# uSDcard.net
KiCad netlist of a schematic drawn in Altium Designer
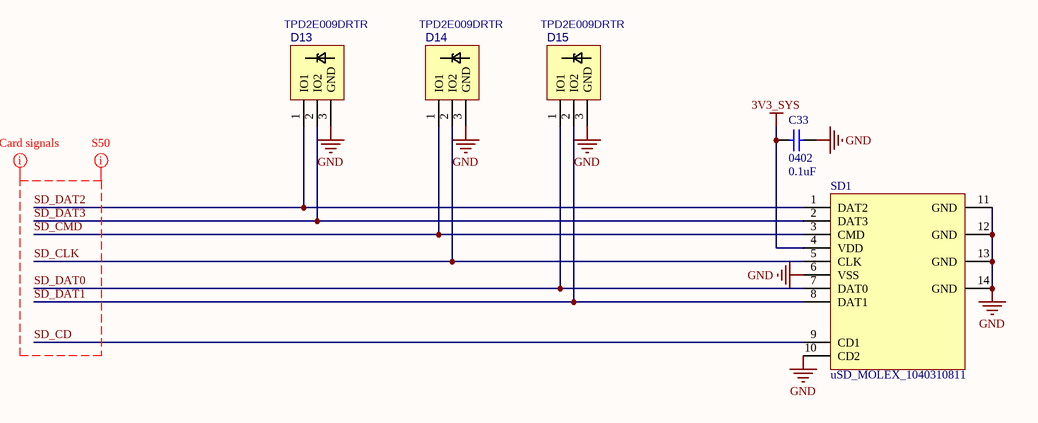
[diagram p0: uSDcard.SchDoc]

(export (version "E")
  (design (tool "Eeschema 10.0.6"))
  (components
    (comp (ref "C33")
      (value "0402")
      (footprint "cap0402")
      (description "standard, non-polarized capacitor")
      (fields (field (name "ALTIUM_VALUE") "0.1uF"))
      (libsource (lib "capacitor") (part "cap"))
    )
    (comp (ref "D13")
      (value "TPD2E009DRTR")
      (footprint "SOT-3")
      (description "ESD Suppressors 2-CH")
      (fields (field (name "MANUFACTURER") "Texas Instruments"))
      (libsource (lib "jetson-nano-baseboard-rev.1.0") (part "TPD2E009"))
    )
    (comp (ref "D14")
      (value "TPD2E009DRTR")
      (footprint "SOT-3")
      (description "ESD Suppressors 2-CH")
      (fields (field (name "MANUFACTURER") "Texas Instruments"))
      (libsource (lib "jetson-nano-baseboard-rev.1.0") (part "TPD2E009"))
    )
    (comp (ref "D15")
      (value "TPD2E009DRTR")
      (footprint "SOT-3")
      (description "ESD Suppressors 2-CH")
      (fields (field (name "MANUFACTURER") "Texas Instruments"))
      (libsource (lib "jetson-nano-baseboard-rev.1.0") (part "TPD2E009"))
    )
    (comp (ref "SD1")
      (value "uSD_MOLEX_1040310811")
      (footprint "uSD_MOLEX_1040310811")
      (libsource (lib "card_holder") (part "uSD_MOLEX_1040310811"))
    )
  )
  (nets
    (net (code "1") (name "/SD_CD") (class "Default")
      (node (ref "SD1") (pin "9") (pinfunction "CD1_9") (pintype "passive"))
    )
    (net (code "2") (name "/SD_CLK") (class "Default")
      (node (ref "D14") (pin "2") (pinfunction "IO2_2") (pintype "passive"))
      (node (ref "SD1") (pin "5") (pinfunction "CLK_5") (pintype "passive"))
    )
    (net (code "3") (name "/SD_CMD") (class "Default")
      (node (ref "D14") (pin "1") (pinfunction "IO1_1") (pintype "passive"))
      (node (ref "SD1") (pin "3") (pinfunction "CMD_3") (pintype "passive"))
    )
    (net (code "4") (name "/SD_DAT0") (class "Default")
      (node (ref "D15") (pin "1") (pinfunction "IO1_1") (pintype "passive"))
      (node (ref "SD1") (pin "7") (pinfunction "DAT0_7") (pintype "passive"))
    )
    (net (code "5") (name "/SD_DAT1") (class "Default")
      (node (ref "D15") (pin "2") (pinfunction "IO2_2") (pintype "passive"))
      (node (ref "SD1") (pin "8") (pinfunction "DAT1_8") (pintype "passive"))
    )
    (net (code "6") (name "/SD_DAT2") (class "Default")
      (node (ref "D13") (pin "1") (pinfunction "IO1_1") (pintype "passive"))
      (node (ref "SD1") (pin "1") (pinfunction "DAT2_1") (pintype "passive"))
    )
    (net (code "7") (name "/SD_DAT3") (class "Default")
      (node (ref "D13") (pin "2") (pinfunction "IO2_2") (pintype "passive"))
      (node (ref "SD1") (pin "2") (pinfunction "DAT3_2") (pintype "passive"))
    )
    (net (code "8") (name "3V3_SYS") (class "Default")
      (node (ref "C33") (pin "1") (pinfunction "1_1") (pintype "passive"))
      (node (ref "SD1") (pin "4") (pinfunction "VDD_4") (pintype "passive"))
    )
    (net (code "9") (name "GND") (class "Default")
      (node (ref "C33") (pin "2") (pinfunction "2_2") (pintype "passive"))
      (node (ref "D13") (pin "3") (pinfunction "GND_3") (pintype "passive"))
      (node (ref "D14") (pin "3") (pinfunction "GND_3") (pintype "passive"))
      (node (ref "D15") (pin "3") (pinfunction "GND_3") (pintype "passive"))
      (node (ref "SD1") (pin "10") (pinfunction "CD2_10") (pintype "passive"))
      (node (ref "SD1") (pin "11") (pinfunction "GND_11") (pintype "passive"))
      (node (ref "SD1") (pin "12") (pinfunction "GND_12") (pintype "passive"))
      (node (ref "SD1") (pin "13") (pinfunction "GND_13") (pintype "passive"))
      (node (ref "SD1") (pin "14") (pinfunction "GND_14") (pintype "passive"))
      (node (ref "SD1") (pin "6") (pinfunction "VSS_6") (pintype "passive"))
    )
  )
)
